# dsp-control.net
KiCad netlist of a schematic drawn in Altium Designer
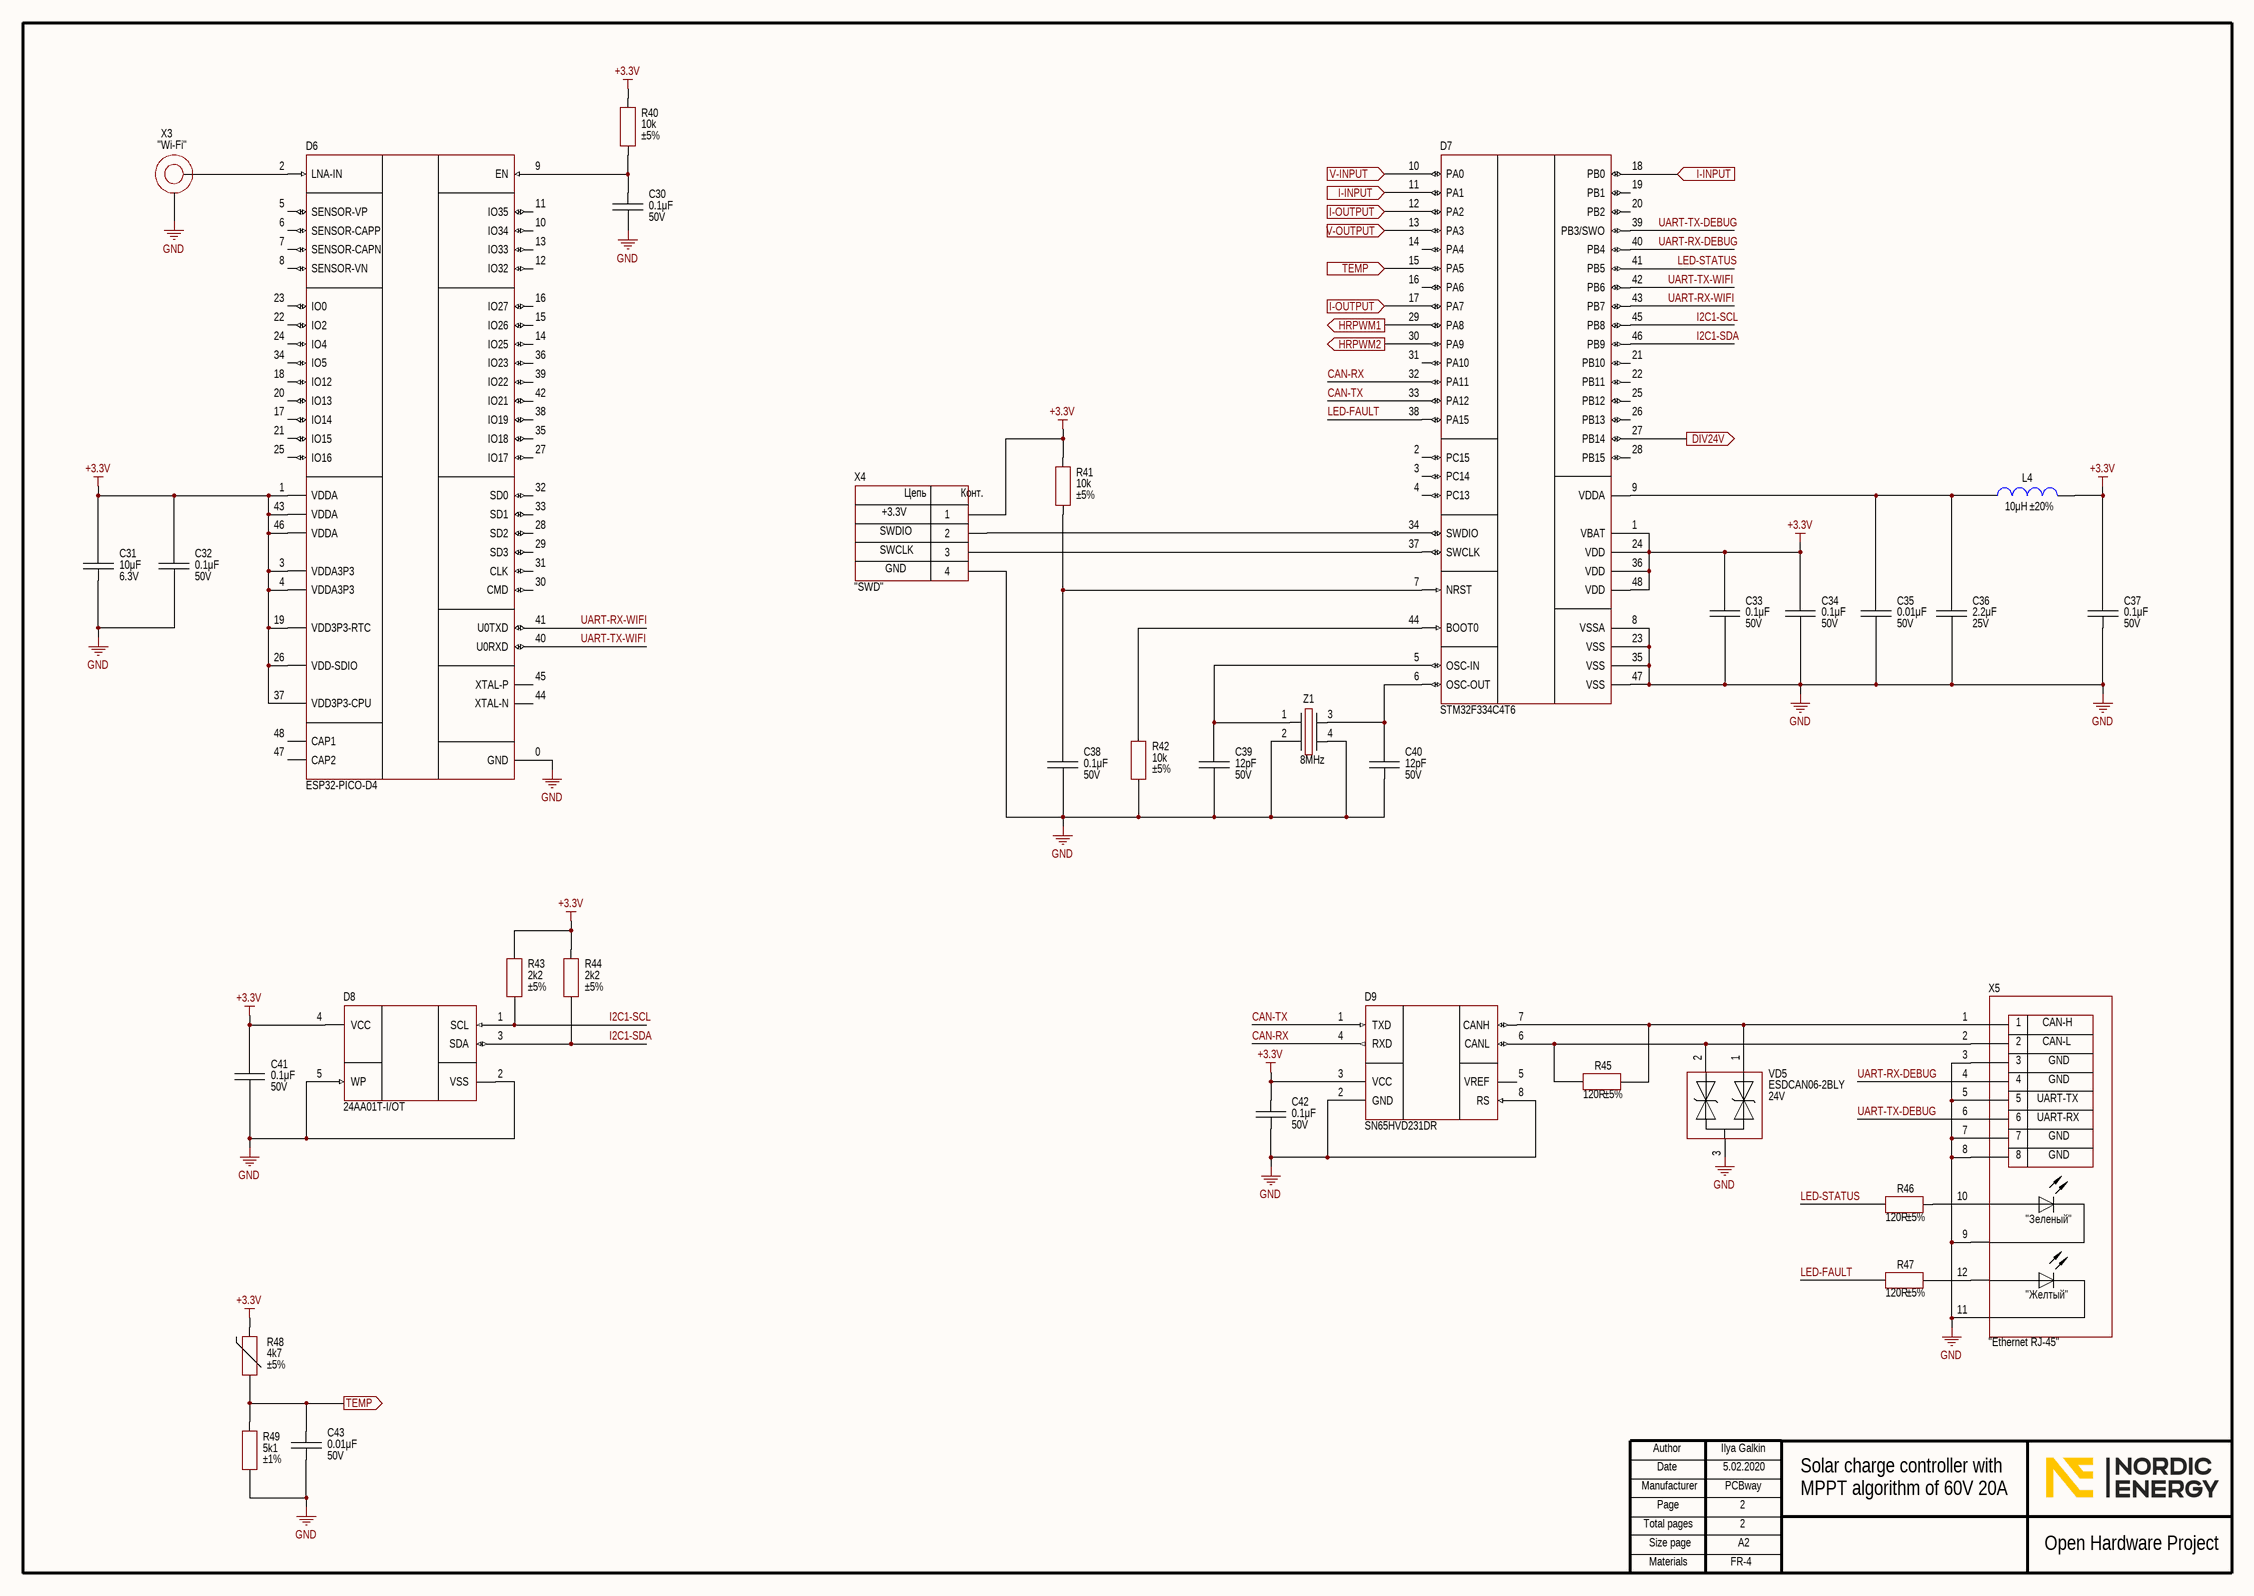
[diagram p0: dsp-control.SchDoc]

(export (version "E")
  (design (tool "Eeschema 10.0.6"))
  (components
    (comp (ref "C30")
      (value "0.1μF")
      (footprint "CAP: 0805")
      (fields
        (field (name "MANUFACTURER") "Samsung")
        (field (name "PARTNUMBER") "CL21B104KBCNFNC")
        (field (name "VALUEMANUFACTURERPARTNUMBER") "Ceramic capacitor, 0.1μF, X7R, ±10%, 50V, 0805, -55...+125°C")
        (field (name "VOLTAGE") "50V")
      )
      (libsource (lib "Capacitor") (part "Ceramic_0805"))
    )
    (comp (ref "C31")
      (value "10μF")
      (footprint "CAP: 0805")
      (fields
        (field (name "MANUFACTURER") "Samsung")
        (field (name "PARTNUMBER") "CL21B106KQQNNNG")
        (field (name "VALUEMANUFACTURERPARTNUMBER") "Ceramic capacitor, 10μF, X7R, ±10%, 6.3V, 0805, -55...+125°C")
        (field (name "VOLTAGE") "6.3V")
      )
      (libsource (lib "Capacitor") (part "Ceramic_0805"))
    )
    (comp (ref "C32")
      (value "0.1μF")
      (footprint "CAP: 0805")
      (fields
        (field (name "MANUFACTURER") "Samsung")
        (field (name "PARTNUMBER") "CL21B104KBCNFNC")
        (field (name "VALUEMANUFACTURERPARTNUMBER") "Ceramic capacitor, 0.1μF, X7R, ±10%, 50V, 0805, -55...+125°C")
        (field (name "VOLTAGE") "50V")
      )
      (libsource (lib "Capacitor") (part "Ceramic_0805"))
    )
    (comp (ref "C33")
      (value "0.1μF")
      (footprint "CAP: 0805")
      (fields
        (field (name "MANUFACTURER") "Samsung")
        (field (name "PARTNUMBER") "CL21B104KBCNFNC")
        (field (name "VALUEMANUFACTURERPARTNUMBER") "Ceramic capacitor, 0.1μF, X7R, ±10%, 50V, 0805, -55...+125°C")
        (field (name "VOLTAGE") "50V")
      )
      (libsource (lib "Capacitor") (part "Ceramic_0805"))
    )
    (comp (ref "C34")
      (value "0.1μF")
      (footprint "CAP: 0805")
      (fields
        (field (name "MANUFACTURER") "Samsung")
        (field (name "PARTNUMBER") "CL21B104KBCNFNC")
        (field (name "VALUEMANUFACTURERPARTNUMBER") "Ceramic capacitor, 0.1μF, X7R, ±10%, 50V, 0805, -55...+125°C")
        (field (name "VOLTAGE") "50V")
      )
      (libsource (lib "Capacitor") (part "Ceramic_0805"))
    )
    (comp (ref "C35")
      (value "0.01μF")
      (footprint "CAP: 0805")
      (fields
        (field (name "MANUFACTURER") "Samsung")
        (field (name "PARTNUMBER") "CL21B103KBANNNC")
        (field (name "VALUEMANUFACTURERPARTNUMBER") "Ceramic capacitor, 0.01μF, X7R, ±10%, 50V, 0805, -55...+125°C")
        (field (name "VOLTAGE") "50V")
      )
      (libsource (lib "Capacitor") (part "Ceramic_0805"))
    )
    (comp (ref "C36")
      (value "2.2μF")
      (footprint "CAP: 0805")
      (fields
        (field (name "MANUFACTURER") "Samsung")
        (field (name "PARTNUMBER") "CL21B225KAFNFNE")
        (field (name "VALUEMANUFACTURERPARTNUMBER") "Ceramic capacitor, 2.2μF, X7R, ±10%, 25V, 0805, -55...+125°C")
        (field (name "VOLTAGE") "25V")
      )
      (libsource (lib "Capacitor") (part "Ceramic_0805"))
    )
    (comp (ref "C37")
      (value "0.1μF")
      (footprint "CAP: 0805")
      (fields
        (field (name "MANUFACTURER") "Samsung")
        (field (name "PARTNUMBER") "CL21B104KBCNFNC")
        (field (name "VALUEMANUFACTURERPARTNUMBER") "Ceramic capacitor, 0.1μF, X7R, ±10%, 50V, 0805, -55...+125°C")
        (field (name "VOLTAGE") "50V")
      )
      (libsource (lib "Capacitor") (part "Ceramic_0805"))
    )
    (comp (ref "C38")
      (value "0.1μF")
      (footprint "CAP: 0805")
      (fields
        (field (name "MANUFACTURER") "Samsung")
        (field (name "PARTNUMBER") "CL21B104KBCNFNC")
        (field (name "VALUEMANUFACTURERPARTNUMBER") "Ceramic capacitor, 0.1μF, X7R, ±10%, 50V, 0805, -55...+125°C")
        (field (name "VOLTAGE") "50V")
      )
      (libsource (lib "Capacitor") (part "Ceramic_0805"))
    )
    (comp (ref "C39")
      (value "12pF")
      (footprint "CAP: 0805")
      (fields
        (field (name "MANUFACTURER") "Samsung")
        (field (name "PARTNUMBER") "CL21C120JBANNNC")
        (field (name "VALUEMANUFACTURERPARTNUMBER") "Ceramic capacitor, 12pF, NPO, ±5%, 50V, 0805, -55...+125°C")
        (field (name "VOLTAGE") "50V")
      )
      (libsource (lib "Capacitor") (part "Ceramic_0805"))
    )
    (comp (ref "C40")
      (value "12pF")
      (footprint "CAP: 0805")
      (fields
        (field (name "MANUFACTURER") "Samsung")
        (field (name "PARTNUMBER") "CL21C120JBANNNC")
        (field (name "VALUEMANUFACTURERPARTNUMBER") "Ceramic capacitor, 12pF, NPO, ±5%, 50V, 0805, -55...+125°C")
        (field (name "VOLTAGE") "50V")
      )
      (libsource (lib "Capacitor") (part "Ceramic_0805"))
    )
    (comp (ref "C41")
      (value "0.1μF")
      (footprint "CAP: 0805")
      (fields
        (field (name "MANUFACTURER") "Samsung")
        (field (name "PARTNUMBER") "CL21B104KBCNFNC")
        (field (name "VALUEMANUFACTURERPARTNUMBER") "Ceramic capacitor, 0.1μF, X7R, ±10%, 50V, 0805, -55...+125°C")
        (field (name "VOLTAGE") "50V")
      )
      (libsource (lib "Capacitor") (part "Ceramic_0805"))
    )
    (comp (ref "C42")
      (value "0.1μF")
      (footprint "CAP: 0805")
      (fields
        (field (name "MANUFACTURER") "Samsung")
        (field (name "PARTNUMBER") "CL21B104KBCNFNC")
        (field (name "VALUEMANUFACTURERPARTNUMBER") "Ceramic capacitor, 0.1μF, X7R, ±10%, 50V, 0805, -55...+125°C")
        (field (name "VOLTAGE") "50V")
      )
      (libsource (lib "Capacitor") (part "Ceramic_0805"))
    )
    (comp (ref "C43")
      (value "0.01μF")
      (footprint "CAP: 0805")
      (fields
        (field (name "MANUFACTURER") "Samsung")
        (field (name "PARTNUMBER") "CL21B103KBANNNC")
        (field (name "VALUEMANUFACTURERPARTNUMBER") "Ceramic capacitor, 0.01μF, X7R, ±10%, 50V, 0805, -55...+125°C")
        (field (name "VOLTAGE") "50V")
      )
      (libsource (lib "Capacitor") (part "Ceramic_0805"))
    )
    (comp (ref "D6")
      (value "~")
      (footprint "48-LGA (7x7)")
      (description "Wi-Fi+BT")
      (fields (field (name "MANUFACTURER") "Espressif Systems") (field (name "PARTNUMBER") "ESP32-PICO-D4"))
      (libsource (lib "IC. RF transceiver") (part "ESP32-PICO-D4"))
    )
    (comp (ref "D7")
      (value "~")
      (footprint "48-LQFP")
      (description "Cortex-M4")
      (fields
        (field (name "MANUFACTURER") "STMicroelectronics")
        (field (name "VALUEMANUFACTURERPARTNUMBER") "IC microcontroller, 32-Bit, Cortex-M4, 72MHz, 16KB, 12KB, 2...3.6V, -40...+85°C, 48-LQFP")
        (field (name "PARTNUMBER") "STM32F334C4T6")
      )
      (libsource (lib "IC. MCU") (part "STM32F334C4T6"))
    )
    (comp (ref "D8")
      (value "~")
      (footprint "SOT23-5")
      (description "EEPROM")
      (fields
        (field (name "MANUFACTURER") "Microchip Technology")
        (field (name "VALUEMANUFACTURERPARTNUMBER") "IC memory, EEPROM, 1KB (128x8), 400 kHz, I2C, 1.7...5.5V, -40...+85°C, SOT-23-5")
        (field (name "PARTNUMBER") "24AA01T-I/OT")
      )
      (libsource (lib "IC. Memory") (part "24AA01T"))
    )
    (comp (ref "D9")
      (value "~")
      (footprint "8-SOIC")
      (description "CAN")
      (fields
        (field (name "MANUFACTURER") "Texas Instruments")
        (field (name "VALUEMANUFACTURERPARTNUMBER") "IC CAN transceiver, 1Mbps, Half-duplex, 3...3.6V, -40...+85°C, 8-SOIC")
        (field (name "PARTNUMBER") "SN65HVD231DR")
      )
      (libsource (lib "IC. Interface") (part "SN65HVD231DR"))
    )
    (comp (ref "L4")
      (value "10μH")
      (footprint "IND: 0805")
      (fields
        (field (name "MANUFACTURER") "Murata Electronics")
        (field (name "PARTNUMBER") "LQM21DH100M70L")
        (field (name "VALUEMANUFACTURERPARTNUMBER") "Fixed inductor, 10μH, ±20%, 0805, 250mA, -55...+125°C")
        (field (name "TOLERANCE") "±20%")
      )
      (libsource (lib "Inductor") (part "Inductor_0805"))
    )
    (comp (ref "R40")
      (value "10k")
      (footprint "RES: 0805")
      (fields
        (field (name "MANUFACTURER") "Yageo")
        (field (name "PARTNUMBER") "RC0805JR-0710KL")
        (field (name "VALUEMANUFACTURERPARTNUMBER") "Resistor film, 10k, ±5%, 0805, 0.125W, -55...+125°C")
        (field (name "TOLERANCE") "±5%")
      )
      (libsource (lib "") (part "Resistor_0805_1"))
    )
    (comp (ref "R41")
      (value "10k")
      (footprint "RES: 0805")
      (fields
        (field (name "MANUFACTURER") "Yageo")
        (field (name "PARTNUMBER") "RC0805JR-0710KL")
        (field (name "VALUEMANUFACTURERPARTNUMBER") "Resistor film, 10k, ±5%, 0805, 0.125W, -55...+125°C")
        (field (name "TOLERANCE") "±5%")
      )
      (libsource (lib "") (part "Resistor_0805_1"))
    )
    (comp (ref "R42")
      (value "10k")
      (footprint "RES: 0805")
      (fields
        (field (name "MANUFACTURER") "Yageo")
        (field (name "PARTNUMBER") "RC0805JR-0710KL")
        (field (name "VALUEMANUFACTURERPARTNUMBER") "Resistor film, 10k, ±5%, 0805, 0.125W, -55...+125°C")
        (field (name "TOLERANCE") "±5%")
      )
      (libsource (lib "") (part "Resistor_0805_1"))
    )
    (comp (ref "R43")
      (value "2k2")
      (footprint "RES: 0805")
      (fields
        (field (name "MANUFACTURER") "Yageo")
        (field (name "PARTNUMBER") "RC0805JR-072K2L")
        (field (name "VALUEMANUFACTURERPARTNUMBER") "Resistor film, 2k2, ±5%, 0805, 0.125W, -55...+125°C")
        (field (name "TOLERANCE") "±5%")
      )
      (libsource (lib "") (part "Resistor_0805_1"))
    )
    (comp (ref "R44")
      (value "2k2")
      (footprint "RES: 0805")
      (fields
        (field (name "MANUFACTURER") "Yageo")
        (field (name "PARTNUMBER") "RC0805JR-072K2L")
        (field (name "VALUEMANUFACTURERPARTNUMBER") "Resistor film, 2k2, ±5%, 0805, 0.125W, -55...+125°C")
        (field (name "TOLERANCE") "±5%")
      )
      (libsource (lib "") (part "Resistor_0805_1"))
    )
    (comp (ref "R45")
      (value "120R")
      (footprint "RES: 0805")
      (fields
        (field (name "MANUFACTURER") "Yageo")
        (field (name "PARTNUMBER") "RC0805JR-07120RL")
        (field (name "VALUEMANUFACTURERPARTNUMBER") "Resistor film, 120R, ±5%, 0805, 0.125W, -55...+125°C")
        (field (name "TOLERANCE") "±5%")
      )
      (libsource (lib "Resistor") (part "Resistor_0805"))
    )
    (comp (ref "R46")
      (value "120R")
      (footprint "RES: 0805")
      (fields
        (field (name "MANUFACTURER") "Yageo")
        (field (name "PARTNUMBER") "RC0805JR-07120RL")
        (field (name "VALUEMANUFACTURERPARTNUMBER") "Resistor film, 120R, ±5%, 0805, 0.125W, -55...+125°C")
        (field (name "TOLERANCE") "±5%")
      )
      (libsource (lib "Resistor") (part "Resistor_0805"))
    )
    (comp (ref "R47")
      (value "120R")
      (footprint "RES: 0805")
      (fields
        (field (name "MANUFACTURER") "Yageo")
        (field (name "PARTNUMBER") "RC0805JR-07120RL")
        (field (name "VALUEMANUFACTURERPARTNUMBER") "Resistor film, 120R, ±5%, 0805, 0.125W, -55...+125°C")
        (field (name "TOLERANCE") "±5%")
      )
      (libsource (lib "Resistor") (part "Resistor_0805"))
    )
    (comp (ref "R48")
      (value "4k7")
      (footprint "RES: 0805")
      (fields
        (field (name "MANUFACTURER") "TDK")
        (field (name "PARTNUMBER") "B57401V2472J062")
        (field (name "VALUEMANUFACTURERPARTNUMBER") "NTC resistor, 4k7, ±5%, 0805, 3650K, -55...+125°C")
        (field (name "TOLERANCE") "±5%")
      )
      (libsource (lib "Resistor") (part "NTC"))
    )
    (comp (ref "R49")
      (value "5k1")
      (footprint "RES: 0805")
      (fields
        (field (name "MANUFACTURER") "Yageo")
        (field (name "PARTNUMBER") "RC0805FR-075K1L")
        (field (name "VALUEMANUFACTURERPARTNUMBER") "Resistor film, 5k1, ±1%, 0805, 0.125W, -55...+125°C")
        (field (name "TOLERANCE") "±1%")
      )
      (libsource (lib "") (part "Resistor_0805_1"))
    )
    (comp (ref "VD5")
      (value "~")
      (footprint "SOT23")
      (fields
        (field (name "MANUFACTURER") "STMicroelectronics")
        (field (name "VALUEMANUFACTURERPARTNUMBER") "TVS diode, 24V, 230W peak, 3A, 13pF, SOT-23, -40...+150°C")
        (field (name "VOLTAGE") "24V")
        (field (name "PARTNUMBER") "ESDCAN06-2BLY")
      )
      (libsource (lib "Diode") (part "TVS_array"))
    )
    (comp (ref "X3")
      (value "~")
      (footprint "CON: u.Fl")
      (fields
        (field (name "MANUFACTURER") "Hirose Electric")
        (field (name "VALUEMANUFACTURERPARTNUMBER") "Connector u.FL, 50 Ohm, 6GHz")
        (field (name "PARTNUMBER") "U.FL-R-SMT(01)")
        (field (name "COMMENTTEXT") "\"Wi-Fi\"")
      )
      (libsource (lib "Connector") (part "Connector_uFL"))
    )
    (comp (ref "X4")
      (value "~")
      (footprint "CON: SM04B-GHS")
      (fields
        (field (name "MANUFACTURER") "JST")
        (field (name "VALUEMANUFACTURERPARTNUMBER") "Connector, 4pin, 1.25mm, 50VDC, 1A")
        (field (name "PARTNUMBER") "SM04B-GHS")
        (field (name "COMMENTTEXT") "\"SWD\"")
      )
      (libsource (lib "Connector") (part "Connector_SM04B"))
    )
    (comp (ref "X5")
      (value "~")
      (footprint "CON: RJ-45 (615008137421 / DS1128-09-S8B8S)")
      (fields
        (field (name "MANUFACTURER") "Wurth")
        (field (name "VALUEMANUFACTURERPARTNUMBER") "Etherner RJ-45 connector")
        (field (name "PARTNUMBER") "615008137421")
        (field (name "COMMENTTEXT") "\"Ethernet RJ-45\"")
      )
      (libsource (lib "Connector") (part "Connector_RJ45"))
    )
    (comp (ref "Z1")
      (value "~")
      (footprint "OSC: 3225")
      (fields
        (field (name "MANUFACTURER") "ECS")
        (field (name "PARTNUMBER") "ECS-80-12-33-JGN-TR")
        (field (name "VALUEMANUFACTURERPARTNUMBER") "Crystal, 8MHz, 12pF, ±30ppm, case 3225, -40...+85°C")
        (field (name "FREQUENCY") "8MHz")
      )
      (libsource (lib "Oscilator") (part "Crystal_3225"))
    )
  )
  (nets
    (net (code "1") (name "+3.3V") (class "Default")
      (node (ref "C31") (pin "2") (pinfunction "2_2") (pintype "power_in"))
      (node (ref "C32") (pin "2") (pinfunction "2_2") (pintype "power_in"))
      (node (ref "C33") (pin "2") (pinfunction "2_2") (pintype "power_in"))
      (node (ref "C34") (pin "2") (pinfunction "2_2") (pintype "power_in"))
      (node (ref "C37") (pin "2") (pinfunction "2_2") (pintype "power_in"))
      (node (ref "C41") (pin "2") (pinfunction "2_2") (pintype "power_in"))
      (node (ref "C42") (pin "2") (pinfunction "2_2") (pintype "power_in"))
      (node (ref "D6") (pin "1") (pinfunction "VDDA_1") (pintype "passive"))
      (node (ref "D6") (pin "19") (pinfunction "VDD3P3-RTC_19") (pintype "passive"))
      (node (ref "D6") (pin "26") (pinfunction "VDD-SDIO_26") (pintype "passive"))
      (node (ref "D6") (pin "3") (pinfunction "VDDA3P3_3") (pintype "passive"))
      (node (ref "D6") (pin "37") (pinfunction "VDD3P3-CPU_37") (pintype "passive"))
      (node (ref "D6") (pin "4") (pinfunction "VDDA3P3_4") (pintype "passive"))
      (node (ref "D6") (pin "43") (pinfunction "VDDA_43") (pintype "passive"))
      (node (ref "D6") (pin "46") (pinfunction "VDDA_46") (pintype "passive"))
      (node (ref "D7") (pin "1") (pinfunction "VBAT_1") (pintype "passive"))
      (node (ref "D7") (pin "24") (pinfunction "VDD_24") (pintype "passive"))
      (node (ref "D7") (pin "36") (pinfunction "VDD_36") (pintype "passive"))
      (node (ref "D7") (pin "48") (pinfunction "VDD_48") (pintype "passive"))
      (node (ref "D8") (pin "4") (pinfunction "VCC_4") (pintype "power_in"))
      (node (ref "D9") (pin "3") (pinfunction "VCC_3") (pintype "passive"))
      (node (ref "L4") (pin "1") (pinfunction "1_1") (pintype "passive"))
      (node (ref "R40") (pin "2") (pinfunction "2_2") (pintype "passive"))
      (node (ref "R41") (pin "2") (pinfunction "2_2") (pintype "passive"))
      (node (ref "R43") (pin "2") (pinfunction "2_2") (pintype "passive"))
      (node (ref "R44") (pin "2") (pinfunction "2_2") (pintype "passive"))
      (node (ref "R48") (pin "2") (pinfunction "2_2") (pintype "passive"))
      (node (ref "X4") (pin "1") (pinfunction "1_1") (pintype "passive"))
    )
    (net (code "2") (name "/CAN-RX") (class "Default")
      (node (ref "D7") (pin "32") (pinfunction "PA11_32") (pintype "bidirectional"))
      (node (ref "D9") (pin "4") (pinfunction "RXD_4") (pintype "output"))
    )
    (net (code "3") (name "/CAN-TX") (class "Default")
      (node (ref "D7") (pin "33") (pinfunction "PA12_33") (pintype "bidirectional"))
      (node (ref "D9") (pin "1") (pinfunction "TXD_1") (pintype "input"))
    )
    (net (code "4") (name "/DIV24V") (class "Default")
      (node (ref "D7") (pin "27") (pinfunction "PB14_27") (pintype "bidirectional"))
    )
    (net (code "5") (name "/HRPWM1") (class "Default")
      (node (ref "D7") (pin "29") (pinfunction "PA8_29") (pintype "bidirectional"))
    )
    (net (code "6") (name "/HRPWM2") (class "Default")
      (node (ref "D7") (pin "30") (pinfunction "PA9_30") (pintype "bidirectional"))
    )
    (net (code "7") (name "/I-INPUT") (class "Default")
      (node (ref "D7") (pin "11") (pinfunction "PA1_11") (pintype "bidirectional"))
      (node (ref "D7") (pin "18") (pinfunction "PB0_18") (pintype "bidirectional"))
    )
    (net (code "8") (name "/I-OUTPUT") (class "Default")
      (node (ref "D7") (pin "12") (pinfunction "PA2_12") (pintype "bidirectional"))
      (node (ref "D7") (pin "17") (pinfunction "PA7_17") (pintype "bidirectional"))
    )
    (net (code "9") (name "/I2C1-SCL") (class "Default")
      (node (ref "D7") (pin "45") (pinfunction "PB8_45") (pintype "bidirectional"))
      (node (ref "D8") (pin "1") (pinfunction "SCL_1") (pintype "input"))
      (node (ref "R43") (pin "1") (pinfunction "1_1") (pintype "passive"))
    )
    (net (code "10") (name "/I2C1-SDA") (class "Default")
      (node (ref "D7") (pin "46") (pinfunction "PB9_46") (pintype "bidirectional"))
      (node (ref "D8") (pin "3") (pinfunction "SDA_3") (pintype "bidirectional"))
      (node (ref "R44") (pin "1") (pinfunction "1_1") (pintype "passive"))
    )
    (net (code "11") (name "/LED-FAULT") (class "Default")
      (node (ref "D7") (pin "38") (pinfunction "PA15_38") (pintype "bidirectional"))
      (node (ref "R47") (pin "2") (pinfunction "2_2") (pintype "passive"))
    )
    (net (code "12") (name "/LED-STATUS") (class "Default")
      (node (ref "D7") (pin "41") (pinfunction "PB5_41") (pintype "bidirectional"))
      (node (ref "R46") (pin "2") (pinfunction "2_2") (pintype "passive"))
    )
    (net (code "13") (name "/TEMP") (class "Default")
      (node (ref "C43") (pin "2") (pinfunction "2_2") (pintype "power_in"))
      (node (ref "D7") (pin "15") (pinfunction "PA5_15") (pintype "bidirectional"))
      (node (ref "R48") (pin "1") (pinfunction "1_1") (pintype "passive"))
      (node (ref "R49") (pin "2") (pinfunction "2_2") (pintype "passive"))
    )
    (net (code "14") (name "/UART-RX-DEBUG") (class "Default")
      (node (ref "D7") (pin "40") (pinfunction "PB4_40") (pintype "bidirectional"))
      (node (ref "X5") (pin "4") (pinfunction "D2_4") (pintype "passive"))
    )
    (net (code "15") (name "/UART-RX-WIFI") (class "Default")
      (node (ref "D6") (pin "41") (pinfunction "U0TXD_41") (pintype "bidirectional"))
      (node (ref "D7") (pin "43") (pinfunction "PB7_43") (pintype "bidirectional"))
    )
    (net (code "16") (name "/UART-TX-DEBUG") (class "Default")
      (node (ref "D7") (pin "39") (pinfunction "PB3/SWO_39") (pintype "bidirectional"))
      (node (ref "X5") (pin "6") (pinfunction "D2_6") (pintype "passive"))
    )
    (net (code "17") (name "/UART-TX-WIFI") (class "Default")
      (node (ref "D6") (pin "40") (pinfunction "U0RXD_40") (pintype "bidirectional"))
      (node (ref "D7") (pin "42") (pinfunction "PB6_42") (pintype "bidirectional"))
    )
    (net (code "18") (name "/V-INPUT") (class "Default")
      (node (ref "D7") (pin "10") (pinfunction "PA0_10") (pintype "bidirectional"))
    )
    (net (code "19") (name "/V-OUTPUT") (class "Default")
      (node (ref "D7") (pin "13") (pinfunction "PA3_13") (pintype "bidirectional"))
    )
    (net (code "20") (name "GND") (class "Default")
      (node (ref "C30") (pin "1") (pinfunction "1_1") (pintype "power_in"))
      (node (ref "C31") (pin "1") (pinfunction "1_1") (pintype "power_in"))
      (node (ref "C32") (pin "1") (pinfunction "1_1") (pintype "power_in"))
      (node (ref "C33") (pin "1") (pinfunction "1_1") (pintype "power_in"))
      (node (ref "C34") (pin "1") (pinfunction "1_1") (pintype "power_in"))
      (node (ref "C35") (pin "1") (pinfunction "1_1") (pintype "power_in"))
      (node (ref "C36") (pin "1") (pinfunction "1_1") (pintype "power_in"))
      (node (ref "C37") (pin "1") (pinfunction "1_1") (pintype "power_in"))
      (node (ref "C38") (pin "1") (pinfunction "1_1") (pintype "power_in"))
      (node (ref "C39") (pin "1") (pinfunction "1_1") (pintype "power_in"))
      (node (ref "C40") (pin "1") (pinfunction "1_1") (pintype "power_in"))
      (node (ref "C41") (pin "1") (pinfunction "1_1") (pintype "power_in"))
      (node (ref "C42") (pin "1") (pinfunction "1_1") (pintype "power_in"))
      (node (ref "C43") (pin "1") (pinfunction "1_1") (pintype "power_in"))
      (node (ref "D6") (pin "0") (pinfunction "GND_0") (pintype "passive"))
      (node (ref "D7") (pin "23") (pinfunction "VSS_23") (pintype "passive"))
      (node (ref "D7") (pin "35") (pinfunction "VSS_35") (pintype "passive"))
      (node (ref "D7") (pin "47") (pinfunction "VSS_47") (pintype "passive"))
      (node (ref "D7") (pin "8") (pinfunction "VSSA_8") (pintype "passive"))
      (node (ref "D8") (pin "2") (pinfunction "VSS_2") (pintype "power_in"))
      (node (ref "D8") (pin "5") (pinfunction "WP_5") (pintype "input"))
      (node (ref "D9") (pin "2") (pinfunction "GND_2") (pintype "passive"))
      (node (ref "D9") (pin "8") (pinfunction "RS_8") (pintype "input"))
      (node (ref "R42") (pin "1") (pinfunction "1_1") (pintype "passive"))
      (node (ref "R49") (pin "1") (pinfunction "1_1") (pintype "passive"))
      (node (ref "VD5") (pin "3") (pintype "passive"))
      (node (ref "X3") (pin "2") (pinfunction "2_2") (pintype "passive"))
      (node (ref "X4") (pin "4") (pinfunction "4_4") (pintype "power_in"))
      (node (ref "X5") (pin "11") (pinfunction "D3_11") (pintype "passive"))
      (node (ref "X5") (pin "3") (pinfunction "D2_3") (pintype "passive"))
      (node (ref "X5") (pin "5") (pinfunction "D2_5") (pintype "passive"))
      (node (ref "X5") (pin "7") (pinfunction "D2_7") (pintype "passive"))
      (node (ref "X5") (pin "8") (pinfunction "D2_8") (pintype "passive"))
      (node (ref "X5") (pin "9") (pinfunction "D2_9") (pintype "passive"))
      (node (ref "Z1") (pin "2") (pinfunction "2_2") (pintype "passive"))
      (node (ref "Z1") (pin "4") (pinfunction "4_4") (pintype "passive"))
    )
    (net (code "21") (name "Net-(D6-EN)") (class "Default")
      (node (ref "C30") (pin "2") (pinfunction "2_2") (pintype "power_in"))
      (node (ref "D6") (pin "9") (pinfunction "EN_9") (pintype "input"))
      (node (ref "R40") (pin "1") (pinfunction "1_1") (pintype "passive"))
    )
    (net (code "22") (name "Net-(D6-LNA-IN)") (class "Default")
      (node (ref "D6") (pin "2") (pinfunction "LNA-IN_2") (pintype "input"))
      (node (ref "X3") (pin "1") (pinfunction "1_1") (pintype "passive"))
    )
    (net (code "23") (name "Net-(D7-BOOT0)") (class "Default")
      (node (ref "D7") (pin "44") (pinfunction "BOOT0_44") (pintype "input"))
      (node (ref "R42") (pin "2") (pinfunction "2_2") (pintype "passive"))
    )
    (net (code "24") (name "Net-(D7-NRST)") (class "Default")
      (node (ref "C38") (pin "2") (pinfunction "2_2") (pintype "power_in"))
      (node (ref "D7") (pin "7") (pinfunction "NRST_7") (pintype "input"))
      (node (ref "R41") (pin "1") (pinfunction "1_1") (pintype "passive"))
    )
    (net (code "25") (name "Net-(D7-OSC-IN)") (class "Default")
      (node (ref "C39") (pin "2") (pinfunction "2_2") (pintype "power_in"))
      (node (ref "D7") (pin "5") (pinfunction "OSC-IN_5") (pintype "bidirectional"))
      (node (ref "Z1") (pin "1") (pinfunction "1_1") (pintype "passive"))
    )
    (net (code "26") (name "Net-(D7-OSC-OUT)") (class "Default")
      (node (ref "C40") (pin "2") (pinfunction "2_2") (pintype "power_in"))
      (node (ref "D7") (pin "6") (pinfunction "OSC-OUT_6") (pintype "bidirectional"))
      (node (ref "Z1") (pin "3") (pinfunction "3_3") (pintype "passive"))
    )
    (net (code "27") (name "Net-(D7-SWCLK)") (class "Default")
      (node (ref "D7") (pin "37") (pinfunction "SWCLK_37") (pintype "bidirectional"))
      (node (ref "X4") (pin "3") (pinfunction "3_3") (pintype "power_in"))
    )
    (net (code "28") (name "Net-(D7-SWDIO)") (class "Default")
      (node (ref "D7") (pin "34") (pinfunction "SWDIO_34") (pintype "bidirectional"))
      (node (ref "X4") (pin "2") (pinfunction "2_2") (pintype "passive"))
    )
    (net (code "29") (name "Net-(D7-VDDA)") (class "Default")
      (node (ref "C35") (pin "2") (pinfunction "2_2") (pintype "power_in"))
      (node (ref "C36") (pin "2") (pinfunction "2_2") (pintype "power_in"))
      (node (ref "D7") (pin "9") (pinfunction "VDDA_9") (pintype "passive"))
      (node (ref "L4") (pin "2") (pinfunction "2_2") (pintype "passive"))
    )
    (net (code "30") (name "Net-(D9-CANH)") (class "Default")
      (node (ref "D9") (pin "7") (pinfunction "CANH_7") (pintype "bidirectional"))
      (node (ref "R45") (pin "1") (pinfunction "1_1") (pintype "passive"))
      (node (ref "VD5") (pin "1") (pintype "passive"))
      (node (ref "X5") (pin "1") (pinfunction "D2_1") (pintype "passive"))
    )
    (net (code "31") (name "Net-(D9-CANL)") (class "Default")
      (node (ref "D9") (pin "6") (pinfunction "CANL_6") (pintype "bidirectional"))
      (node (ref "R45") (pin "2") (pinfunction "2_2") (pintype "passive"))
      (node (ref "VD5") (pin "2") (pintype "passive"))
      (node (ref "X5") (pin "2") (pinfunction "D2_2") (pintype "passive"))
    )
    (net (code "32") (name "Net-(X5-D1)") (class "Default")
      (node (ref "R46") (pin "1") (pinfunction "1_1") (pintype "passive"))
      (node (ref "X5") (pin "10") (pinfunction "D1_10") (pintype "passive"))
    )
    (net (code "33") (name "Net-(X5-D4)") (class "Default")
      (node (ref "R47") (pin "1") (pinfunction "1_1") (pintype "passive"))
      (node (ref "X5") (pin "12") (pinfunction "D4_12") (pintype "passive"))
    )
    (net (code "34") (name "unconnected-(D6-CAP1-Pad48)") (class "Default")
      (node (ref "D6") (pin "48") (pinfunction "CAP1_48") (pintype "passive"))
    )
    (net (code "35") (name "unconnected-(D6-CAP2-Pad47)") (class "Default")
      (node (ref "D6") (pin "47") (pinfunction "CAP2_47") (pintype "passive"))
    )
    (net (code "36") (name "unconnected-(D6-CLK-Pad31)") (class "Default")
      (node (ref "D6") (pin "31") (pinfunction "CLK_31") (pintype "bidirectional"))
    )
    (net (code "37") (name "unconnected-(D6-CMD-Pad30)") (class "Default")
      (node (ref "D6") (pin "30") (pinfunction "CMD_30") (pintype "bidirectional"))
    )
    (net (code "38") (name "unconnected-(D6-IO0-Pad23)") (class "Default")
      (node (ref "D6") (pin "23") (pinfunction "IO0_23") (pintype "bidirectional"))
    )
    (net (code "39") (name "unconnected-(D6-IO2-Pad22)") (class "Default")
      (node (ref "D6") (pin "22") (pinfunction "IO2_22") (pintype "bidirectional"))
    )
    (net (code "40") (name "unconnected-(D6-IO4-Pad24)") (class "Default")
      (node (ref "D6") (pin "24") (pinfunction "IO4_24") (pintype "bidirectional"))
    )
    (net (code "41") (name "unconnected-(D6-IO5-Pad34)") (class "Default")
      (node (ref "D6") (pin "34") (pinfunction "IO5_34") (pintype "bidirectional"))
    )
    (net (code "42") (name "unconnected-(D6-IO12-Pad18)") (class "Default")
      (node (ref "D6") (pin "18") (pinfunction "IO12_18") (pintype "bidirectional"))
    )
    (net (code "43") (name "unconnected-(D6-IO13-Pad20)") (class "Default")
      (node (ref "D6") (pin "20") (pinfunction "IO13_20") (pintype "bidirectional"))
    )
    (net (code "44") (name "unconnected-(D6-IO14-Pad17)") (class "Default")
      (node (ref "D6") (pin "17") (pinfunction "IO14_17") (pintype "bidirectional"))
    )
    (net (code "45") (name "unconnected-(D6-IO15-Pad21)") (class "Default")
      (node (ref "D6") (pin "21") (pinfunction "IO15_21") (pintype "bidirectional"))
    )
    (net (code "46") (name "unconnected-(D6-IO16-Pad25)") (class "Default")
      (node (ref "D6") (pin "25") (pinfunction "IO16_25") (pintype "bidirectional"))
    )
    (net (code "47") (name "unconnected-(D6-IO17-Pad27)") (class "Default")
      (node (ref "D6") (pin "27") (pinfunction "IO17_27") (pintype "bidirectional"))
    )
    (net (code "48") (name "unconnected-(D6-IO18-Pad35)") (class "Default")
      (node (ref "D6") (pin "35") (pinfunction "IO18_35") (pintype "bidirectional"))
    )
    (net (code "49") (name "unconnected-(D6-IO19-Pad38)") (class "Default")
      (node (ref "D6") (pin "38") (pinfunction "IO19_38") (pintype "bidirectional"))
    )
    (net (code "50") (name "unconnected-(D6-IO21-Pad42)") (class "Default")
      (node (ref "D6") (pin "42") (pinfunction "IO21_42") (pintype "bidirectional"))
    )
    (net (code "51") (name "unconnected-(D6-IO22-Pad39)") (class "Default")
      (node (ref "D6") (pin "39") (pinfunction "IO22_39") (pintype "bidirectional"))
    )
    (net (code "52") (name "unconnected-(D6-IO23-Pad36)") (class "Default")
      (node (ref "D6") (pin "36") (pinfunction "IO23_36") (pintype "bidirectional"))
    )
    (net (code "53") (name "unconnected-(D6-IO25-Pad14)") (class "Default")
      (node (ref "D6") (pin "14") (pinfunction "IO25_14") (pintype "bidirectional"))
    )
    (net (code "54") (name "unconnected-(D6-IO26-Pad15)") (class "Default")
      (node (ref "D6") (pin "15") (pinfunction "IO26_15") (pintype "bidirectional"))
    )
    (net (code "55") (name "unconnected-(D6-IO27-Pad16)") (class "Default")
      (node (ref "D6") (pin "16") (pinfunction "IO27_16") (pintype "bidirectional"))
    )
    (net (code "56") (name "unconnected-(D6-IO32-Pad12)") (class "Default")
      (node (ref "D6") (pin "12") (pinfunction "IO32_12") (pintype "bidirectional"))
    )
    (net (code "57") (name "unconnected-(D6-IO33-Pad13)") (class "Default")
      (node (ref "D6") (pin "13") (pinfunction "IO33_13") (pintype "bidirectional"))
    )
    (net (code "58") (name "unconnected-(D6-IO34-Pad10)") (class "Default")
      (node (ref "D6") (pin "10") (pinfunction "IO34_10") (pintype "bidirectional"))
    )
    (net (code "59") (name "unconnected-(D6-IO35-Pad11)") (class "Default")
      (node (ref "D6") (pin "11") (pinfunction "IO35_11") (pintype "bidirectional"))
    )
    (net (code "60") (name "unconnected-(D6-SD0-Pad32)") (class "Default")
      (node (ref "D6") (pin "32") (pinfunction "SD0_32") (pintype "bidirectional"))
    )
    (net (code "61") (name "unconnected-(D6-SD1-Pad33)") (class "Default")
      (node (ref "D6") (pin "33") (pinfunction "SD1_33") (pintype "bidirectional"))
    )
    (net (code "62") (name "unconnected-(D6-SD2-Pad28)") (class "Default")
      (node (ref "D6") (pin "28") (pinfunction "SD2_28") (pintype "bidirectional"))
    )
    (net (code "63") (name "unconnected-(D6-SD3-Pad29)") (class "Default")
      (node (ref "D6") (pin "29") (pinfunction "SD3_29") (pintype "bidirectional"))
    )
    (net (code "64") (name "unconnected-(D6-SENSOR-CAPN-Pad7)") (class "Default")
      (node (ref "D6") (pin "7") (pinfunction "SENSOR-CAPN_7") (pintype "bidirectional"))
    )
    (net (code "65") (name "unconnected-(D6-SENSOR-CAPP-Pad6)") (class "Default")
      (node (ref "D6") (pin "6") (pinfunction "SENSOR-CAPP_6") (pintype "bidirectional"))
    )
    (net (code "66") (name "unconnected-(D6-SENSOR-VN-Pad8)") (class "Default")
      (node (ref "D6") (pin "8") (pinfunction "SENSOR-VN_8") (pintype "bidirectional"))
    )
    (net (code "67") (name "unconnected-(D6-SENSOR-VP-Pad5)") (class "Default")
      (node (ref "D6") (pin "5") (pinfunction "SENSOR-VP_5") (pintype "bidirectional"))
    )
    (net (code "68") (name "unconnected-(D6-XTAL-N-Pad44)") (class "Default")
      (node (ref "D6") (pin "44") (pinfunction "XTAL-N_44") (pintype "passive"))
    )
    (net (code "69") (name "unconnected-(D6-XTAL-P-Pad45)") (class "Default")
      (node (ref "D6") (pin "45") (pinfunction "XTAL-P_45") (pintype "passive"))
    )
    (net (code "70") (name "unconnected-(D7-PA4-Pad14)") (class "Default")
      (node (ref "D7") (pin "14") (pinfunction "PA4_14") (pintype "bidirectional"))
    )
    (net (code "71") (name "unconnected-(D7-PA6-Pad16)") (class "Default")
      (node (ref "D7") (pin "16") (pinfunction "PA6_16") (pintype "bidirectional"))
    )
    (net (code "72") (name "unconnected-(D7-PA10-Pad31)") (class "Default")
      (node (ref "D7") (pin "31") (pinfunction "PA10_31") (pintype "bidirectional"))
    )
    (net (code "73") (name "unconnected-(D7-PB1-Pad19)") (class "Default")
      (node (ref "D7") (pin "19") (pinfunction "PB1_19") (pintype "bidirectional"))
    )
    (net (code "74") (name "unconnected-(D7-PB2-Pad20)") (class "Default")
      (node (ref "D7") (pin "20") (pinfunction "PB2_20") (pintype "bidirectional"))
    )
    (net (code "75") (name "unconnected-(D7-PB10-Pad21)") (class "Default")
      (node (ref "D7") (pin "21") (pinfunction "PB10_21") (pintype "bidirectional"))
    )
    (net (code "76") (name "unconnected-(D7-PB11-Pad22)") (class "Default")
      (node (ref "D7") (pin "22") (pinfunction "PB11_22") (pintype "bidirectional"))
    )
    (net (code "77") (name "unconnected-(D7-PB12-Pad25)") (class "Default")
      (node (ref "D7") (pin "25") (pinfunction "PB12_25") (pintype "bidirectional"))
    )
    (net (code "78") (name "unconnected-(D7-PB13-Pad26)") (class "Default")
      (node (ref "D7") (pin "26") (pinfunction "PB13_26") (pintype "bidirectional"))
    )
    (net (code "79") (name "unconnected-(D7-PB15-Pad28)") (class "Default")
      (node (ref "D7") (pin "28") (pinfunction "PB15_28") (pintype "bidirectional"))
    )
    (net (code "80") (name "unconnected-(D7-PC13-Pad4)") (class "Default")
      (node (ref "D7") (pin "4") (pinfunction "PC13_4") (pintype "bidirectional"))
    )
    (net (code "81") (name "unconnected-(D7-PC14-Pad3)") (class "Default")
      (node (ref "D7") (pin "3") (pinfunction "PC14_3") (pintype "bidirectional"))
    )
    (net (code "82") (name "unconnected-(D7-PC15-Pad2)") (class "Default")
      (node (ref "D7") (pin "2") (pinfunction "PC15_2") (pintype "bidirectional"))
    )
    (net (code "83") (name "unconnected-(D9-VREF-Pad5)") (class "Default")
      (node (ref "D9") (pin "5") (pinfunction "VREF_5") (pintype "passive"))
    )
  )
)
